# power.net
KiCad netlist of a schematic drawn in EAGLE
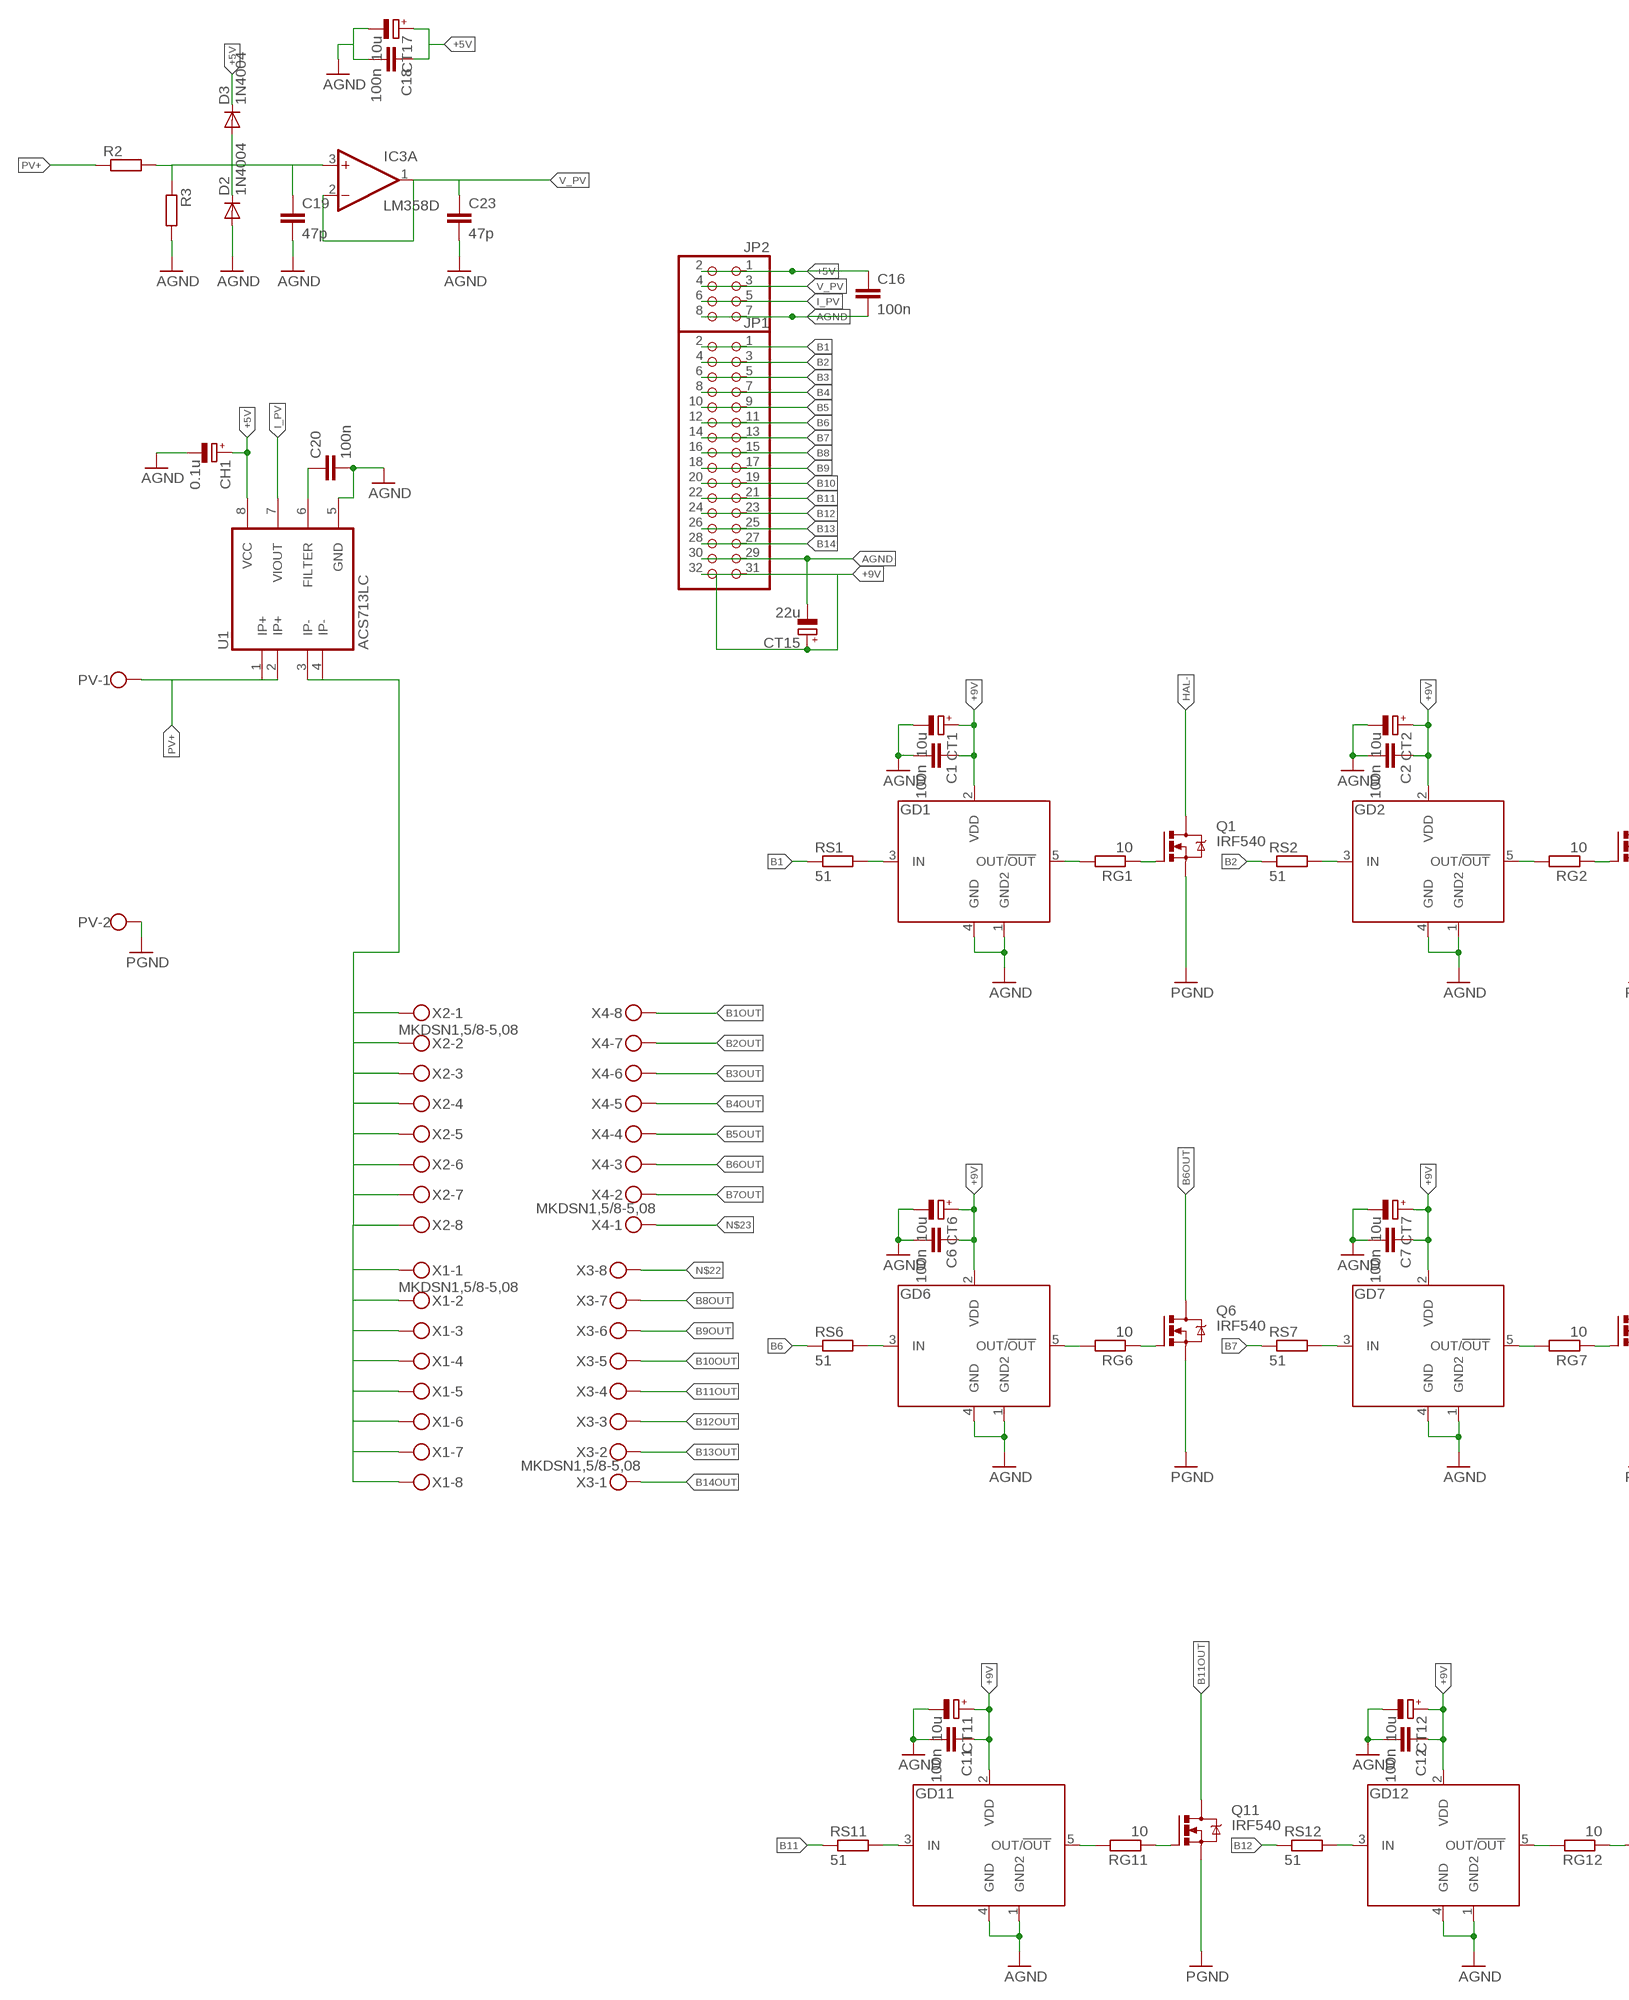
[diagram p0: schematic, sheet 1, part 1 of 2]
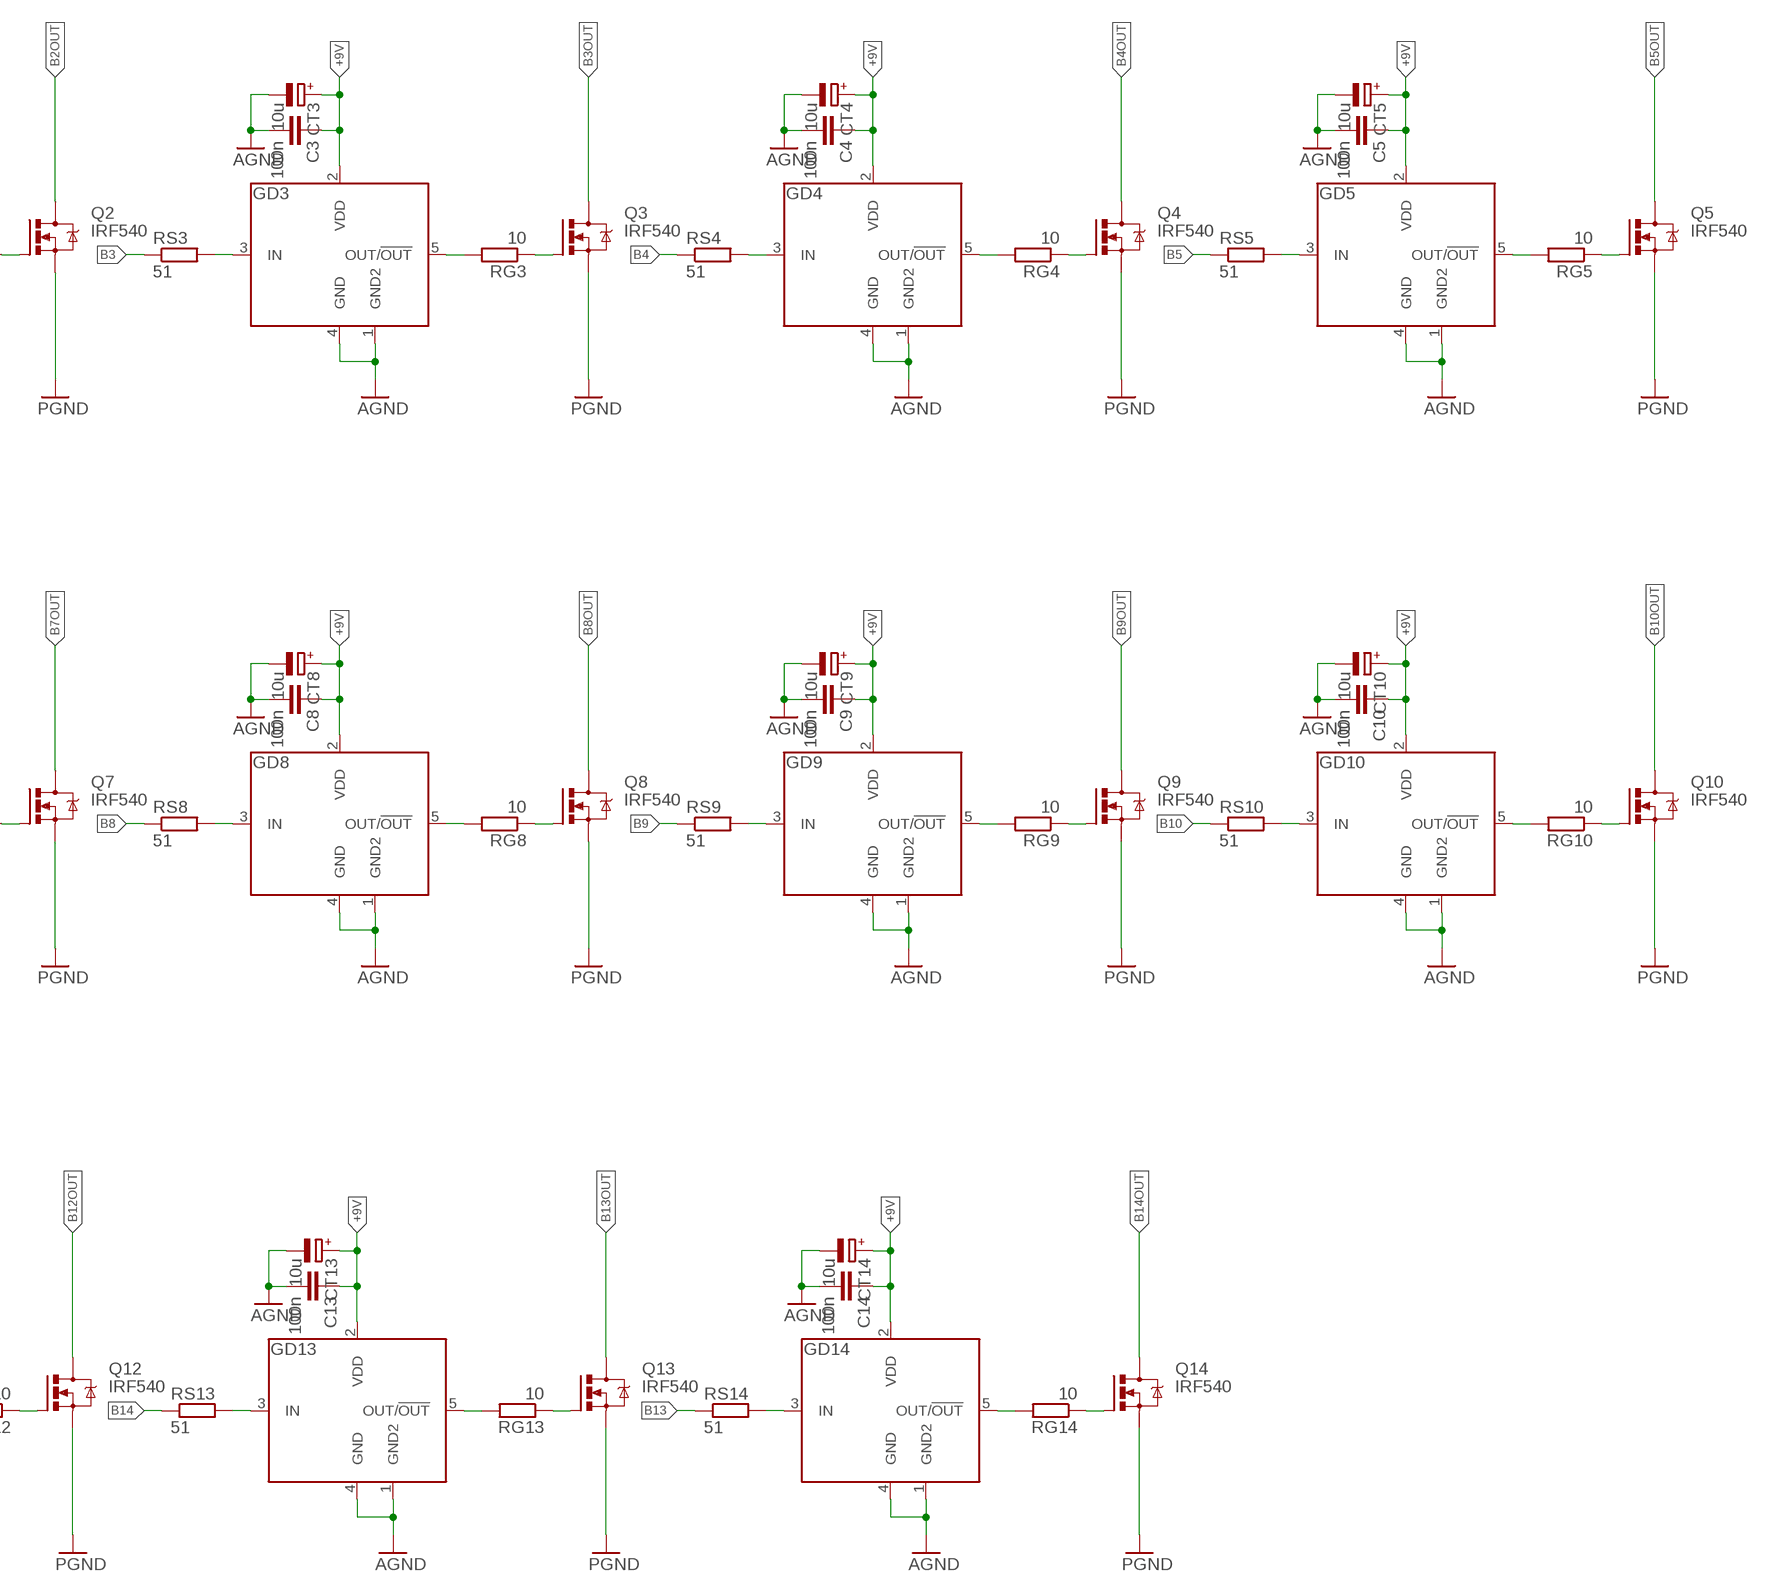
[diagram p1: schematic, sheet 1, part 2 of 2]

(export (version "E")
  (design (tool "Eeschema 10.0.6"))
  (components
    (comp (ref "C1")
      (value "100n")
      (footprint "eagle-import:C0603")
      (libsource (lib "eagle-import") (part "C-EUC0603"))
    )
    (comp (ref "C2")
      (value "100n")
      (footprint "eagle-import:C0603")
      (libsource (lib "eagle-import") (part "C-EUC0603"))
    )
    (comp (ref "C3")
      (value "100n")
      (footprint "eagle-import:C0603")
      (libsource (lib "eagle-import") (part "C-EUC0603"))
    )
    (comp (ref "C4")
      (value "100n")
      (footprint "eagle-import:C0603")
      (libsource (lib "eagle-import") (part "C-EUC0603"))
    )
    (comp (ref "C5")
      (value "100n")
      (footprint "eagle-import:C0603")
      (libsource (lib "eagle-import") (part "C-EUC0603"))
    )
    (comp (ref "C6")
      (value "100n")
      (footprint "eagle-import:C0603")
      (libsource (lib "eagle-import") (part "C-EUC0603"))
    )
    (comp (ref "C7")
      (value "100n")
      (footprint "eagle-import:C0603")
      (libsource (lib "eagle-import") (part "C-EUC0603"))
    )
    (comp (ref "C8")
      (value "100n")
      (footprint "eagle-import:C0603")
      (libsource (lib "eagle-import") (part "C-EUC0603"))
    )
    (comp (ref "C9")
      (value "100n")
      (footprint "eagle-import:C0603")
      (libsource (lib "eagle-import") (part "C-EUC0603"))
    )
    (comp (ref "C10")
      (value "100n")
      (footprint "eagle-import:C0603")
      (libsource (lib "eagle-import") (part "C-EUC0603"))
    )
    (comp (ref "C11")
      (value "100n")
      (footprint "eagle-import:C0603")
      (libsource (lib "eagle-import") (part "C-EUC0603"))
    )
    (comp (ref "C12")
      (value "100n")
      (footprint "eagle-import:C0603")
      (libsource (lib "eagle-import") (part "C-EUC0603"))
    )
    (comp (ref "C13")
      (value "100n")
      (footprint "eagle-import:C0603")
      (libsource (lib "eagle-import") (part "C-EUC0603"))
    )
    (comp (ref "C14")
      (value "100n")
      (footprint "eagle-import:C0603")
      (libsource (lib "eagle-import") (part "C-EUC0603"))
    )
    (comp (ref "C16")
      (value "100n")
      (footprint "eagle-import:C0603")
      (libsource (lib "eagle-import") (part "C-EUC0603"))
    )
    (comp (ref "C18")
      (value "100n")
      (footprint "eagle-import:C0603")
      (libsource (lib "eagle-import") (part "C-EUC0603"))
    )
    (comp (ref "C19")
      (value "47p")
      (footprint "eagle-import:C0603")
      (libsource (lib "eagle-import") (part "C-EUC0603"))
    )
    (comp (ref "C20")
      (value "100n")
      (footprint "eagle-import:C0603")
      (libsource (lib "eagle-import") (part "C-EUC0603"))
    )
    (comp (ref "C23")
      (value "47p")
      (footprint "eagle-import:C0603")
      (libsource (lib "eagle-import") (part "C-EUC0603"))
    )
    (comp (ref "CH1")
      (value "0.1u")
      (footprint "eagle-import:B_3528-21W")
      (libsource (lib "eagle-import") (part "CPOL-EUB/3528-21W"))
    )
    (comp (ref "CT1")
      (value "10u")
      (footprint "eagle-import:B_3528-21W")
      (libsource (lib "eagle-import") (part "CPOL-EUB/3528-21W"))
    )
    (comp (ref "CT2")
      (value "10u")
      (footprint "eagle-import:B_3528-21W")
      (libsource (lib "eagle-import") (part "CPOL-EUB/3528-21W"))
    )
    (comp (ref "CT3")
      (value "10u")
      (footprint "eagle-import:B_3528-21W")
      (libsource (lib "eagle-import") (part "CPOL-EUB/3528-21W"))
    )
    (comp (ref "CT4")
      (value "10u")
      (footprint "eagle-import:B_3528-21W")
      (libsource (lib "eagle-import") (part "CPOL-EUB/3528-21W"))
    )
    (comp (ref "CT5")
      (value "10u")
      (footprint "eagle-import:B_3528-21W")
      (libsource (lib "eagle-import") (part "CPOL-EUB/3528-21W"))
    )
    (comp (ref "CT6")
      (value "10u")
      (footprint "eagle-import:B_3528-21W")
      (libsource (lib "eagle-import") (part "CPOL-EUB/3528-21W"))
    )
    (comp (ref "CT7")
      (value "10u")
      (footprint "eagle-import:B_3528-21W")
      (libsource (lib "eagle-import") (part "CPOL-EUB/3528-21W"))
    )
    (comp (ref "CT8")
      (value "10u")
      (footprint "eagle-import:B_3528-21W")
      (libsource (lib "eagle-import") (part "CPOL-EUB/3528-21W"))
    )
    (comp (ref "CT9")
      (value "10u")
      (footprint "eagle-import:B_3528-21W")
      (libsource (lib "eagle-import") (part "CPOL-EUB/3528-21W"))
    )
    (comp (ref "CT10")
      (value "10u")
      (footprint "eagle-import:B_3528-21W")
      (libsource (lib "eagle-import") (part "CPOL-EUB/3528-21W"))
    )
    (comp (ref "CT11")
      (value "10u")
      (footprint "eagle-import:B_3528-21W")
      (libsource (lib "eagle-import") (part "CPOL-EUB/3528-21W"))
    )
    (comp (ref "CT12")
      (value "10u")
      (footprint "eagle-import:B_3528-21W")
      (libsource (lib "eagle-import") (part "CPOL-EUB/3528-21W"))
    )
    (comp (ref "CT13")
      (value "10u")
      (footprint "eagle-import:B_3528-21W")
      (libsource (lib "eagle-import") (part "CPOL-EUB/3528-21W"))
    )
    (comp (ref "CT14")
      (value "10u")
      (footprint "eagle-import:B_3528-21W")
      (libsource (lib "eagle-import") (part "CPOL-EUB/3528-21W"))
    )
    (comp (ref "CT15")
      (value "22u")
      (footprint "eagle-import:B_3528-21W")
      (libsource (lib "eagle-import") (part "CPOL-EUB/3528-21W"))
    )
    (comp (ref "CT17")
      (value "10u")
      (footprint "eagle-import:B_3528-21W")
      (libsource (lib "eagle-import") (part "CPOL-EUB/3528-21W"))
    )
    (comp (ref "D2")
      (value "1N4004")
      (footprint "eagle-import:DO214AC")
      (libsource (lib "eagle-import") (part "1N4004"))
    )
    (comp (ref "D3")
      (value "1N4004")
      (footprint "eagle-import:DO214AC")
      (libsource (lib "eagle-import") (part "1N4004"))
    )
    (comp (ref "GD1")
      (value "MCP1415/16")
      (footprint "eagle-import:SOT23-5L")
      (libsource (lib "eagle-import") (part "MCP1415/16"))
    )
    (comp (ref "GD2")
      (value "MCP1415/16")
      (footprint "eagle-import:SOT23-5L")
      (libsource (lib "eagle-import") (part "MCP1415/16"))
    )
    (comp (ref "GD3")
      (value "MCP1415/16")
      (footprint "eagle-import:SOT23-5L")
      (libsource (lib "eagle-import") (part "MCP1415/16"))
    )
    (comp (ref "GD4")
      (value "MCP1415/16")
      (footprint "eagle-import:SOT23-5L")
      (libsource (lib "eagle-import") (part "MCP1415/16"))
    )
    (comp (ref "GD5")
      (value "MCP1415/16")
      (footprint "eagle-import:SOT23-5L")
      (libsource (lib "eagle-import") (part "MCP1415/16"))
    )
    (comp (ref "GD6")
      (value "MCP1415/16")
      (footprint "eagle-import:SOT23-5L")
      (libsource (lib "eagle-import") (part "MCP1415/16"))
    )
    (comp (ref "GD7")
      (value "MCP1415/16")
      (footprint "eagle-import:SOT23-5L")
      (libsource (lib "eagle-import") (part "MCP1415/16"))
    )
    (comp (ref "GD8")
      (value "MCP1415/16")
      (footprint "eagle-import:SOT23-5L")
      (libsource (lib "eagle-import") (part "MCP1415/16"))
    )
    (comp (ref "GD9")
      (value "MCP1415/16")
      (footprint "eagle-import:SOT23-5L")
      (libsource (lib "eagle-import") (part "MCP1415/16"))
    )
    (comp (ref "GD10")
      (value "MCP1415/16")
      (footprint "eagle-import:SOT23-5L")
      (libsource (lib "eagle-import") (part "MCP1415/16"))
    )
    (comp (ref "GD11")
      (value "MCP1415/16")
      (footprint "eagle-import:SOT23-5L")
      (libsource (lib "eagle-import") (part "MCP1415/16"))
    )
    (comp (ref "GD12")
      (value "MCP1415/16")
      (footprint "eagle-import:SOT23-5L")
      (libsource (lib "eagle-import") (part "MCP1415/16"))
    )
    (comp (ref "GD13")
      (value "MCP1415/16")
      (footprint "eagle-import:SOT23-5L")
      (libsource (lib "eagle-import") (part "MCP1415/16"))
    )
    (comp (ref "GD14")
      (value "MCP1415/16")
      (footprint "eagle-import:SOT23-5L")
      (libsource (lib "eagle-import") (part "MCP1415/16"))
    )
    (comp (ref "IC3")
      (value "LM358D")
      (footprint "eagle-import:SO08")
      (libsource (lib "eagle-import") (part "LM358D"))
    )
    (comp (ref "JP1")
      (value "PINHD-2X16")
      (footprint "eagle-import:2X16")
      (libsource (lib "eagle-import") (part "PINHD-2X16"))
    )
    (comp (ref "JP2")
      (value "PINHD-2X4")
      (footprint "eagle-import:2X04")
      (libsource (lib "eagle-import") (part "PINHD-2X4"))
    )
    (comp (ref "PV")
      (value "W237-102")
      (footprint "eagle-import:W237-102")
      (fields (field (name "MPN") "237-102"))
      (libsource (lib "eagle-import") (part "W237-102"))
    )
    (comp (ref "Q1")
      (value "IRF540")
      (footprint "eagle-import:TO220BV")
      (libsource (lib "eagle-import") (part "IRF540"))
    )
    (comp (ref "Q2")
      (value "IRF540")
      (footprint "eagle-import:TO220BV")
      (libsource (lib "eagle-import") (part "IRF540"))
    )
    (comp (ref "Q3")
      (value "IRF540")
      (footprint "eagle-import:TO220BV")
      (libsource (lib "eagle-import") (part "IRF540"))
    )
    (comp (ref "Q4")
      (value "IRF540")
      (footprint "eagle-import:TO220BV")
      (libsource (lib "eagle-import") (part "IRF540"))
    )
    (comp (ref "Q5")
      (value "IRF540")
      (footprint "eagle-import:TO220BV")
      (libsource (lib "eagle-import") (part "IRF540"))
    )
    (comp (ref "Q6")
      (value "IRF540")
      (footprint "eagle-import:TO220BV")
      (libsource (lib "eagle-import") (part "IRF540"))
    )
    (comp (ref "Q7")
      (value "IRF540")
      (footprint "eagle-import:TO220BV")
      (libsource (lib "eagle-import") (part "IRF540"))
    )
    (comp (ref "Q8")
      (value "IRF540")
      (footprint "eagle-import:TO220BV")
      (libsource (lib "eagle-import") (part "IRF540"))
    )
    (comp (ref "Q9")
      (value "IRF540")
      (footprint "eagle-import:TO220BV")
      (libsource (lib "eagle-import") (part "IRF540"))
    )
    (comp (ref "Q10")
      (value "IRF540")
      (footprint "eagle-import:TO220BV")
      (libsource (lib "eagle-import") (part "IRF540"))
    )
    (comp (ref "Q11")
      (value "IRF540")
      (footprint "eagle-import:TO220BV")
      (libsource (lib "eagle-import") (part "IRF540"))
    )
    (comp (ref "Q12")
      (value "IRF540")
      (footprint "eagle-import:TO220BV")
      (libsource (lib "eagle-import") (part "IRF540"))
    )
    (comp (ref "Q13")
      (value "IRF540")
      (footprint "eagle-import:TO220BV")
      (libsource (lib "eagle-import") (part "IRF540"))
    )
    (comp (ref "Q14")
      (value "IRF540")
      (footprint "eagle-import:TO220BV")
      (libsource (lib "eagle-import") (part "IRF540"))
    )
    (comp (ref "R2")
      (value "R-EU_R1206")
      (footprint "eagle-import:R1206")
      (libsource (lib "eagle-import") (part "R-EU_R1206"))
    )
    (comp (ref "R3")
      (value "R-EU_R1206")
      (footprint "eagle-import:R1206")
      (libsource (lib "eagle-import") (part "R-EU_R1206"))
    )
    (comp (ref "RG1")
      (value "10")
      (footprint "eagle-import:R1206")
      (libsource (lib "eagle-import") (part "R-EU_R1206"))
    )
    (comp (ref "RG2")
      (value "10")
      (footprint "eagle-import:R1206")
      (libsource (lib "eagle-import") (part "R-EU_R1206"))
    )
    (comp (ref "RG3")
      (value "10")
      (footprint "eagle-import:R1206")
      (libsource (lib "eagle-import") (part "R-EU_R1206"))
    )
    (comp (ref "RG4")
      (value "10")
      (footprint "eagle-import:R1206")
      (libsource (lib "eagle-import") (part "R-EU_R1206"))
    )
    (comp (ref "RG5")
      (value "10")
      (footprint "eagle-import:R1206")
      (libsource (lib "eagle-import") (part "R-EU_R1206"))
    )
    (comp (ref "RG6")
      (value "10")
      (footprint "eagle-import:R1206")
      (libsource (lib "eagle-import") (part "R-EU_R1206"))
    )
    (comp (ref "RG7")
      (value "10")
      (footprint "eagle-import:R1206")
      (libsource (lib "eagle-import") (part "R-EU_R1206"))
    )
    (comp (ref "RG8")
      (value "10")
      (footprint "eagle-import:R1206")
      (libsource (lib "eagle-import") (part "R-EU_R1206"))
    )
    (comp (ref "RG9")
      (value "10")
      (footprint "eagle-import:R1206")
      (libsource (lib "eagle-import") (part "R-EU_R1206"))
    )
    (comp (ref "RG10")
      (value "10")
      (footprint "eagle-import:R1206")
      (libsource (lib "eagle-import") (part "R-EU_R1206"))
    )
    (comp (ref "RG11")
      (value "10")
      (footprint "eagle-import:R1206")
      (libsource (lib "eagle-import") (part "R-EU_R1206"))
    )
    (comp (ref "RG12")
      (value "10")
      (footprint "eagle-import:R1206")
      (libsource (lib "eagle-import") (part "R-EU_R1206"))
    )
    (comp (ref "RG13")
      (value "10")
      (footprint "eagle-import:R1206")
      (libsource (lib "eagle-import") (part "R-EU_R1206"))
    )
    (comp (ref "RG14")
      (value "10")
      (footprint "eagle-import:R1206")
      (libsource (lib "eagle-import") (part "R-EU_R1206"))
    )
    (comp (ref "RS1")
      (value "51")
      (footprint "eagle-import:R1206")
      (libsource (lib "eagle-import") (part "R-EU_R1206"))
    )
    (comp (ref "RS2")
      (value "51")
      (footprint "eagle-import:R1206")
      (libsource (lib "eagle-import") (part "R-EU_R1206"))
    )
    (comp (ref "RS3")
      (value "51")
      (footprint "eagle-import:R1206")
      (libsource (lib "eagle-import") (part "R-EU_R1206"))
    )
    (comp (ref "RS4")
      (value "51")
      (footprint "eagle-import:R1206")
      (libsource (lib "eagle-import") (part "R-EU_R1206"))
    )
    (comp (ref "RS5")
      (value "51")
      (footprint "eagle-import:R1206")
      (libsource (lib "eagle-import") (part "R-EU_R1206"))
    )
    (comp (ref "RS6")
      (value "51")
      (footprint "eagle-import:R1206")
      (libsource (lib "eagle-import") (part "R-EU_R1206"))
    )
    (comp (ref "RS7")
      (value "51")
      (footprint "eagle-import:R1206")
      (libsource (lib "eagle-import") (part "R-EU_R1206"))
    )
    (comp (ref "RS8")
      (value "51")
      (footprint "eagle-import:R1206")
      (libsource (lib "eagle-import") (part "R-EU_R1206"))
    )
    (comp (ref "RS9")
      (value "51")
      (footprint "eagle-import:R1206")
      (libsource (lib "eagle-import") (part "R-EU_R1206"))
    )
    (comp (ref "RS10")
      (value "51")
      (footprint "eagle-import:R1206")
      (libsource (lib "eagle-import") (part "R-EU_R1206"))
    )
    (comp (ref "RS11")
      (value "51")
      (footprint "eagle-import:R1206")
      (libsource (lib "eagle-import") (part "R-EU_R1206"))
    )
    (comp (ref "RS12")
      (value "51")
      (footprint "eagle-import:R1206")
      (libsource (lib "eagle-import") (part "R-EU_R1206"))
    )
    (comp (ref "RS13")
      (value "51")
      (footprint "eagle-import:R1206")
      (libsource (lib "eagle-import") (part "R-EU_R1206"))
    )
    (comp (ref "RS14")
      (value "51")
      (footprint "eagle-import:R1206")
      (libsource (lib "eagle-import") (part "R-EU_R1206"))
    )
    (comp (ref "U1")
      (value "ACS713LC")
      (footprint "eagle-import:SO08")
      (libsource (lib "eagle-import") (part "ACS713LC"))
    )
    (comp (ref "X1")
      (value "MKDSN1,5/8-5,08")
      (footprint "eagle-import:MKDSN1,5_8-5,08")
      (libsource (lib "eagle-import") (part "MKDSN1,5/8-5,08"))
    )
    (comp (ref "X2")
      (value "MKDSN1,5/8-5,08")
      (footprint "eagle-import:MKDSN1,5_8-5,08")
      (libsource (lib "eagle-import") (part "MKDSN1,5/8-5,08"))
    )
    (comp (ref "X3")
      (value "MKDSN1,5/8-5,08")
      (footprint "eagle-import:MKDSN1,5_8-5,08")
      (libsource (lib "eagle-import") (part "MKDSN1,5/8-5,08"))
    )
    (comp (ref "X4")
      (value "MKDSN1,5/8-5,08")
      (footprint "eagle-import:MKDSN1,5_8-5,08")
      (libsource (lib "eagle-import") (part "MKDSN1,5/8-5,08"))
    )
  )
  (nets
    (net (code "1") (name "+5V") (class "Default")
      (node (ref "C16") (pin "1") (pinfunction "1_1") (pintype "passive"))
      (node (ref "C18") (pin "1") (pinfunction "1_1") (pintype "passive"))
      (node (ref "CH1") (pin "+") (pinfunction "+_+") (pintype "passive"))
      (node (ref "CT17") (pin "+") (pinfunction "+_+") (pintype "passive"))
      (node (ref "D3") (pin "C") (pinfunction "C_C") (pintype "passive"))
      (node (ref "JP2") (pin "1") (pinfunction "1_1") (pintype "passive"))
      (node (ref "JP2") (pin "2") (pinfunction "2_2") (pintype "passive"))
      (node (ref "U1") (pin "8") (pinfunction "VCC_8") (pintype "power_in"))
    )
    (net (code "2") (name "+9V") (class "Default")
      (node (ref "C1") (pin "1") (pinfunction "1_1") (pintype "passive"))
      (node (ref "C10") (pin "1") (pinfunction "1_1") (pintype "passive"))
      (node (ref "C11") (pin "1") (pinfunction "1_1") (pintype "passive"))
      (node (ref "C12") (pin "1") (pinfunction "1_1") (pintype "passive"))
      (node (ref "C13") (pin "1") (pinfunction "1_1") (pintype "passive"))
      (node (ref "C14") (pin "1") (pinfunction "1_1") (pintype "passive"))
      (node (ref "C2") (pin "1") (pinfunction "1_1") (pintype "passive"))
      (node (ref "C3") (pin "1") (pinfunction "1_1") (pintype "passive"))
      (node (ref "C4") (pin "1") (pinfunction "1_1") (pintype "passive"))
      (node (ref "C5") (pin "1") (pinfunction "1_1") (pintype "passive"))
      (node (ref "C6") (pin "1") (pinfunction "1_1") (pintype "passive"))
      (node (ref "C7") (pin "1") (pinfunction "1_1") (pintype "passive"))
      (node (ref "C8") (pin "1") (pinfunction "1_1") (pintype "passive"))
      (node (ref "C9") (pin "1") (pinfunction "1_1") (pintype "passive"))
      (node (ref "CT1") (pin "+") (pinfunction "+_+") (pintype "passive"))
      (node (ref "CT10") (pin "+") (pinfunction "+_+") (pintype "passive"))
      (node (ref "CT11") (pin "+") (pinfunction "+_+") (pintype "passive"))
      (node (ref "CT12") (pin "+") (pinfunction "+_+") (pintype "passive"))
      (node (ref "CT13") (pin "+") (pinfunction "+_+") (pintype "passive"))
      (node (ref "CT14") (pin "+") (pinfunction "+_+") (pintype "passive"))
      (node (ref "CT15") (pin "+") (pinfunction "+_+") (pintype "passive"))
      (node (ref "CT2") (pin "+") (pinfunction "+_+") (pintype "passive"))
      (node (ref "CT3") (pin "+") (pinfunction "+_+") (pintype "passive"))
      (node (ref "CT4") (pin "+") (pinfunction "+_+") (pintype "passive"))
      (node (ref "CT5") (pin "+") (pinfunction "+_+") (pintype "passive"))
      (node (ref "CT6") (pin "+") (pinfunction "+_+") (pintype "passive"))
      (node (ref "CT7") (pin "+") (pinfunction "+_+") (pintype "passive"))
      (node (ref "CT8") (pin "+") (pinfunction "+_+") (pintype "passive"))
      (node (ref "CT9") (pin "+") (pinfunction "+_+") (pintype "passive"))
      (node (ref "GD1") (pin "2") (pinfunction "VDD_2") (pintype "power_in"))
      (node (ref "GD10") (pin "2") (pinfunction "VDD_2") (pintype "power_in"))
      (node (ref "GD11") (pin "2") (pinfunction "VDD_2") (pintype "power_in"))
      (node (ref "GD12") (pin "2") (pinfunction "VDD_2") (pintype "power_in"))
      (node (ref "GD13") (pin "2") (pinfunction "VDD_2") (pintype "power_in"))
      (node (ref "GD14") (pin "2") (pinfunction "VDD_2") (pintype "power_in"))
      (node (ref "GD2") (pin "2") (pinfunction "VDD_2") (pintype "power_in"))
      (node (ref "GD3") (pin "2") (pinfunction "VDD_2") (pintype "power_in"))
      (node (ref "GD4") (pin "2") (pinfunction "VDD_2") (pintype "power_in"))
      (node (ref "GD5") (pin "2") (pinfunction "VDD_2") (pintype "power_in"))
      (node (ref "GD6") (pin "2") (pinfunction "VDD_2") (pintype "power_in"))
      (node (ref "GD7") (pin "2") (pinfunction "VDD_2") (pintype "power_in"))
      (node (ref "GD8") (pin "2") (pinfunction "VDD_2") (pintype "power_in"))
      (node (ref "GD9") (pin "2") (pinfunction "VDD_2") (pintype "power_in"))
      (node (ref "JP1") (pin "31") (pinfunction "31_31") (pintype "passive"))
      (node (ref "JP1") (pin "32") (pinfunction "32_32") (pintype "passive"))
    )
    (net (code "3") (name "AGND") (class "Default")
      (node (ref "C1") (pin "2") (pinfunction "2_2") (pintype "passive"))
      (node (ref "C10") (pin "2") (pinfunction "2_2") (pintype "passive"))
      (node (ref "C11") (pin "2") (pinfunction "2_2") (pintype "passive"))
      (node (ref "C12") (pin "2") (pinfunction "2_2") (pintype "passive"))
      (node (ref "C13") (pin "2") (pinfunction "2_2") (pintype "passive"))
      (node (ref "C14") (pin "2") (pinfunction "2_2") (pintype "passive"))
      (node (ref "C16") (pin "2") (pinfunction "2_2") (pintype "passive"))
      (node (ref "C18") (pin "2") (pinfunction "2_2") (pintype "passive"))
      (node (ref "C19") (pin "2") (pinfunction "2_2") (pintype "passive"))
      (node (ref "C2") (pin "2") (pinfunction "2_2") (pintype "passive"))
      (node (ref "C20") (pin "2") (pinfunction "2_2") (pintype "passive"))
      (node (ref "C23") (pin "2") (pinfunction "2_2") (pintype "passive"))
      (node (ref "C3") (pin "2") (pinfunction "2_2") (pintype "passive"))
      (node (ref "C4") (pin "2") (pinfunction "2_2") (pintype "passive"))
      (node (ref "C5") (pin "2") (pinfunction "2_2") (pintype "passive"))
      (node (ref "C6") (pin "2") (pinfunction "2_2") (pintype "passive"))
      (node (ref "C7") (pin "2") (pinfunction "2_2") (pintype "passive"))
      (node (ref "C8") (pin "2") (pinfunction "2_2") (pintype "passive"))
      (node (ref "C9") (pin "2") (pinfunction "2_2") (pintype "passive"))
      (node (ref "CH1") (pin "-") (pinfunction "-_-") (pintype "passive"))
      (node (ref "CT1") (pin "-") (pinfunction "-_-") (pintype "passive"))
      (node (ref "CT10") (pin "-") (pinfunction "-_-") (pintype "passive"))
      (node (ref "CT11") (pin "-") (pinfunction "-_-") (pintype "passive"))
      (node (ref "CT12") (pin "-") (pinfunction "-_-") (pintype "passive"))
      (node (ref "CT13") (pin "-") (pinfunction "-_-") (pintype "passive"))
      (node (ref "CT14") (pin "-") (pinfunction "-_-") (pintype "passive"))
      (node (ref "CT15") (pin "-") (pinfunction "-_-") (pintype "passive"))
      (node (ref "CT17") (pin "-") (pinfunction "-_-") (pintype "passive"))
      (node (ref "CT2") (pin "-") (pinfunction "-_-") (pintype "passive"))
      (node (ref "CT3") (pin "-") (pinfunction "-_-") (pintype "passive"))
      (node (ref "CT4") (pin "-") (pinfunction "-_-") (pintype "passive"))
      (node (ref "CT5") (pin "-") (pinfunction "-_-") (pintype "passive"))
      (node (ref "CT6") (pin "-") (pinfunction "-_-") (pintype "passive"))
      (node (ref "CT7") (pin "-") (pinfunction "-_-") (pintype "passive"))
      (node (ref "CT8") (pin "-") (pinfunction "-_-") (pintype "passive"))
      (node (ref "CT9") (pin "-") (pinfunction "-_-") (pintype "passive"))
      (node (ref "D2") (pin "A") (pinfunction "A_A") (pintype "passive"))
      (node (ref "GD1") (pin "1") (pinfunction "GND2_1") (pintype "bidirectional"))
      (node (ref "GD1") (pin "4") (pinfunction "GND_4") (pintype "power_in"))
      (node (ref "GD10") (pin "1") (pinfunction "GND2_1") (pintype "bidirectional"))
      (node (ref "GD10") (pin "4") (pinfunction "GND_4") (pintype "power_in"))
      (node (ref "GD11") (pin "1") (pinfunction "GND2_1") (pintype "bidirectional"))
      (node (ref "GD11") (pin "4") (pinfunction "GND_4") (pintype "power_in"))
      (node (ref "GD12") (pin "1") (pinfunction "GND2_1") (pintype "bidirectional"))
      (node (ref "GD12") (pin "4") (pinfunction "GND_4") (pintype "power_in"))
      (node (ref "GD13") (pin "1") (pinfunction "GND2_1") (pintype "bidirectional"))
      (node (ref "GD13") (pin "4") (pinfunction "GND_4") (pintype "power_in"))
      (node (ref "GD14") (pin "1") (pinfunction "GND2_1") (pintype "bidirectional"))
      (node (ref "GD14") (pin "4") (pinfunction "GND_4") (pintype "power_in"))
      (node (ref "GD2") (pin "1") (pinfunction "GND2_1") (pintype "bidirectional"))
      (node (ref "GD2") (pin "4") (pinfunction "GND_4") (pintype "power_in"))
      (node (ref "GD3") (pin "1") (pinfunction "GND2_1") (pintype "bidirectional"))
      (node (ref "GD3") (pin "4") (pinfunction "GND_4") (pintype "power_in"))
      (node (ref "GD4") (pin "1") (pinfunction "GND2_1") (pintype "bidirectional"))
      (node (ref "GD4") (pin "4") (pinfunction "GND_4") (pintype "power_in"))
      (node (ref "GD5") (pin "1") (pinfunction "GND2_1") (pintype "bidirectional"))
      (node (ref "GD5") (pin "4") (pinfunction "GND_4") (pintype "power_in"))
      (node (ref "GD6") (pin "1") (pinfunction "GND2_1") (pintype "bidirectional"))
      (node (ref "GD6") (pin "4") (pinfunction "GND_4") (pintype "power_in"))
      (node (ref "GD7") (pin "1") (pinfunction "GND2_1") (pintype "bidirectional"))
      (node (ref "GD7") (pin "4") (pinfunction "GND_4") (pintype "power_in"))
      (node (ref "GD8") (pin "1") (pinfunction "GND2_1") (pintype "bidirectional"))
      (node (ref "GD8") (pin "4") (pinfunction "GND_4") (pintype "power_in"))
      (node (ref "GD9") (pin "1") (pinfunction "GND2_1") (pintype "bidirectional"))
      (node (ref "GD9") (pin "4") (pinfunction "GND_4") (pintype "power_in"))
      (node (ref "JP1") (pin "29") (pinfunction "29_29") (pintype "passive"))
      (node (ref "JP1") (pin "30") (pinfunction "30_30") (pintype "passive"))
      (node (ref "JP2") (pin "7") (pinfunction "7_7") (pintype "passive"))
      (node (ref "JP2") (pin "8") (pinfunction "8_8") (pintype "passive"))
      (node (ref "R3") (pin "2") (pinfunction "2_2") (pintype "passive"))
      (node (ref "U1") (pin "5") (pinfunction "GND_5") (pintype "power_in"))
    )
    (net (code "4") (name "B1") (class "Default")
      (node (ref "JP1") (pin "1") (pinfunction "1_1") (pintype "passive"))
      (node (ref "JP1") (pin "2") (pinfunction "2_2") (pintype "passive"))
      (node (ref "RS1") (pin "1") (pinfunction "1_1") (pintype "passive"))
    )
    (net (code "5") (name "B1OUT") (class "Default")
      (node (ref "X4") (pin "8") (pinfunction "KL_8") (pintype "passive"))
    )
    (net (code "6") (name "B2") (class "Default")
      (node (ref "JP1") (pin "3") (pinfunction "3_3") (pintype "passive"))
      (node (ref "JP1") (pin "4") (pinfunction "4_4") (pintype "passive"))
      (node (ref "RS2") (pin "1") (pinfunction "1_1") (pintype "passive"))
    )
    (net (code "7") (name "B2OUT") (class "Default")
      (node (ref "Q2") (pin "D") (pinfunction "D_D") (pintype "passive"))
      (node (ref "X4") (pin "7") (pinfunction "KL_7") (pintype "passive"))
    )
    (net (code "8") (name "B3") (class "Default")
      (node (ref "JP1") (pin "5") (pinfunction "5_5") (pintype "passive"))
      (node (ref "JP1") (pin "6") (pinfunction "6_6") (pintype "passive"))
      (node (ref "RS3") (pin "1") (pinfunction "1_1") (pintype "passive"))
    )
    (net (code "9") (name "B3OUT") (class "Default")
      (node (ref "Q3") (pin "D") (pinfunction "D_D") (pintype "passive"))
      (node (ref "X4") (pin "6") (pinfunction "KL_6") (pintype "passive"))
    )
    (net (code "10") (name "B4") (class "Default")
      (node (ref "JP1") (pin "7") (pinfunction "7_7") (pintype "passive"))
      (node (ref "JP1") (pin "8") (pinfunction "8_8") (pintype "passive"))
      (node (ref "RS4") (pin "1") (pinfunction "1_1") (pintype "passive"))
    )
    (net (code "11") (name "B4OUT") (class "Default")
      (node (ref "Q4") (pin "D") (pinfunction "D_D") (pintype "passive"))
      (node (ref "X4") (pin "5") (pinfunction "KL_5") (pintype "passive"))
    )
    (net (code "12") (name "B5") (class "Default")
      (node (ref "JP1") (pin "10") (pinfunction "10_10") (pintype "passive"))
      (node (ref "JP1") (pin "9") (pinfunction "9_9") (pintype "passive"))
      (node (ref "RS5") (pin "1") (pinfunction "1_1") (pintype "passive"))
    )
    (net (code "13") (name "B5OUT") (class "Default")
      (node (ref "Q5") (pin "D") (pinfunction "D_D") (pintype "passive"))
      (node (ref "X4") (pin "4") (pinfunction "KL_4") (pintype "passive"))
    )
    (net (code "14") (name "B6") (class "Default")
      (node (ref "JP1") (pin "11") (pinfunction "11_11") (pintype "passive"))
      (node (ref "JP1") (pin "12") (pinfunction "12_12") (pintype "passive"))
      (node (ref "RS6") (pin "1") (pinfunction "1_1") (pintype "passive"))
    )
    (net (code "15") (name "B6OUT") (class "Default")
      (node (ref "Q6") (pin "D") (pinfunction "D_D") (pintype "passive"))
      (node (ref "X4") (pin "3") (pinfunction "KL_3") (pintype "passive"))
    )
    (net (code "16") (name "B7") (class "Default")
      (node (ref "JP1") (pin "13") (pinfunction "13_13") (pintype "passive"))
      (node (ref "JP1") (pin "14") (pinfunction "14_14") (pintype "passive"))
      (node (ref "RS7") (pin "1") (pinfunction "1_1") (pintype "passive"))
    )
    (net (code "17") (name "B7OUT") (class "Default")
      (node (ref "Q7") (pin "D") (pinfunction "D_D") (pintype "passive"))
      (node (ref "X4") (pin "2") (pinfunction "KL_2") (pintype "passive"))
    )
    (net (code "18") (name "B8") (class "Default")
      (node (ref "JP1") (pin "15") (pinfunction "15_15") (pintype "passive"))
      (node (ref "JP1") (pin "16") (pinfunction "16_16") (pintype "passive"))
      (node (ref "RS8") (pin "1") (pinfunction "1_1") (pintype "passive"))
    )
    (net (code "19") (name "B8OUT") (class "Default")
      (node (ref "Q8") (pin "D") (pinfunction "D_D") (pintype "passive"))
      (node (ref "X3") (pin "7") (pinfunction "KL_7") (pintype "passive"))
    )
    (net (code "20") (name "B9") (class "Default")
      (node (ref "JP1") (pin "17") (pinfunction "17_17") (pintype "passive"))
      (node (ref "JP1") (pin "18") (pinfunction "18_18") (pintype "passive"))
      (node (ref "RS9") (pin "1") (pinfunction "1_1") (pintype "passive"))
    )
    (net (code "21") (name "B9OUT") (class "Default")
      (node (ref "Q9") (pin "D") (pinfunction "D_D") (pintype "passive"))
      (node (ref "X3") (pin "6") (pinfunction "KL_6") (pintype "passive"))
    )
    (net (code "22") (name "B10") (class "Default")
      (node (ref "JP1") (pin "19") (pinfunction "19_19") (pintype "passive"))
      (node (ref "JP1") (pin "20") (pinfunction "20_20") (pintype "passive"))
      (node (ref "RS10") (pin "1") (pinfunction "1_1") (pintype "passive"))
    )
    (net (code "23") (name "B10OUT") (class "Default")
      (node (ref "Q10") (pin "D") (pinfunction "D_D") (pintype "passive"))
      (node (ref "X3") (pin "5") (pinfunction "KL_5") (pintype "passive"))
    )
    (net (code "24") (name "B11") (class "Default")
      (node (ref "JP1") (pin "21") (pinfunction "21_21") (pintype "passive"))
      (node (ref "JP1") (pin "22") (pinfunction "22_22") (pintype "passive"))
      (node (ref "RS11") (pin "1") (pinfunction "1_1") (pintype "passive"))
    )
    (net (code "25") (name "B11OUT") (class "Default")
      (node (ref "Q11") (pin "D") (pinfunction "D_D") (pintype "passive"))
      (node (ref "X3") (pin "4") (pinfunction "KL_4") (pintype "passive"))
    )
    (net (code "26") (name "B12") (class "Default")
      (node (ref "JP1") (pin "23") (pinfunction "23_23") (pintype "passive"))
      (node (ref "JP1") (pin "24") (pinfunction "24_24") (pintype "passive"))
      (node (ref "RS12") (pin "1") (pinfunction "1_1") (pintype "passive"))
    )
    (net (code "27") (name "B12OUT") (class "Default")
      (node (ref "Q12") (pin "D") (pinfunction "D_D") (pintype "passive"))
      (node (ref "X3") (pin "3") (pinfunction "KL_3") (pintype "passive"))
    )
    (net (code "28") (name "B13") (class "Default")
      (node (ref "JP1") (pin "25") (pinfunction "25_25") (pintype "passive"))
      (node (ref "JP1") (pin "26") (pinfunction "26_26") (pintype "passive"))
      (node (ref "RS14") (pin "1") (pinfunction "1_1") (pintype "passive"))
    )
    (net (code "29") (name "B13OUT") (class "Default")
      (node (ref "Q13") (pin "D") (pinfunction "D_D") (pintype "passive"))
      (node (ref "X3") (pin "2") (pinfunction "KL_2") (pintype "passive"))
    )
    (net (code "30") (name "B14") (class "Default")
      (node (ref "JP1") (pin "27") (pinfunction "27_27") (pintype "passive"))
      (node (ref "JP1") (pin "28") (pinfunction "28_28") (pintype "passive"))
      (node (ref "RS13") (pin "1") (pinfunction "1_1") (pintype "passive"))
    )
    (net (code "31") (name "B14OUT") (class "Default")
      (node (ref "Q14") (pin "D") (pinfunction "D_D") (pintype "passive"))
      (node (ref "X3") (pin "1") (pinfunction "KL_1") (pintype "passive"))
    )
    (net (code "32") (name "HAL-") (class "Default")
      (node (ref "Q1") (pin "D") (pinfunction "D_D") (pintype "passive"))
      (node (ref "U1") (pin "3") (pinfunction "IP-_3") (pintype "passive"))
      (node (ref "U1") (pin "4") (pinfunction "IP-_4") (pintype "passive"))
      (node (ref "X1") (pin "1") (pinfunction "KL_1") (pintype "passive"))
      (node (ref "X1") (pin "2") (pinfunction "KL_2") (pintype "passive"))
      (node (ref "X1") (pin "3") (pinfunction "KL_3") (pintype "passive"))
      (node (ref "X1") (pin "4") (pinfunction "KL_4") (pintype "passive"))
      (node (ref "X1") (pin "5") (pinfunction "KL_5") (pintype "passive"))
      (node (ref "X1") (pin "6") (pinfunction "KL_6") (pintype "passive"))
      (node (ref "X1") (pin "7") (pinfunction "KL_7") (pintype "passive"))
      (node (ref "X1") (pin "8") (pinfunction "KL_8") (pintype "passive"))
      (node (ref "X2") (pin "1") (pinfunction "KL_1") (pintype "passive"))
      (node (ref "X2") (pin "2") (pinfunction "KL_2") (pintype "passive"))
      (node (ref "X2") (pin "3") (pinfunction "KL_3") (pintype "passive"))
      (node (ref "X2") (pin "4") (pinfunction "KL_4") (pintype "passive"))
      (node (ref "X2") (pin "5") (pinfunction "KL_5") (pintype "passive"))
      (node (ref "X2") (pin "6") (pinfunction "KL_6") (pintype "passive"))
      (node (ref "X2") (pin "7") (pinfunction "KL_7") (pintype "passive"))
      (node (ref "X2") (pin "8") (pinfunction "KL_8") (pintype "passive"))
    )
    (net (code "33") (name "I_PV") (class "Default")
      (node (ref "JP2") (pin "5") (pinfunction "5_5") (pintype "passive"))
      (node (ref "JP2") (pin "6") (pinfunction "6_6") (pintype "passive"))
      (node (ref "U1") (pin "7") (pinfunction "VIOUT_7") (pintype "output"))
    )
    (net (code "34") (name "N$22") (class "Default")
      (node (ref "X3") (pin "8") (pinfunction "KL_8") (pintype "passive"))
    )
    (net (code "35") (name "N$23") (class "Default")
      (node (ref "X4") (pin "1") (pinfunction "KL_1") (pintype "passive"))
    )
    (net (code "36") (name "Net-(GD1-IN)") (class "Default")
      (node (ref "GD1") (pin "3") (pinfunction "IN_3") (pintype "input"))
      (node (ref "RS1") (pin "2") (pinfunction "2_2") (pintype "passive"))
    )
    (net (code "37") (name "Net-(GD1-OUT{slash}~{OUT})") (class "Default")
      (node (ref "GD1") (pin "5") (pinfunction "OUT/~{OUT}_5") (pintype "output"))
      (node (ref "RG1") (pin "2") (pinfunction "2_2") (pintype "passive"))
    )
    (net (code "38") (name "Net-(GD2-IN)") (class "Default")
      (node (ref "GD2") (pin "3") (pinfunction "IN_3") (pintype "input"))
      (node (ref "RS2") (pin "2") (pinfunction "2_2") (pintype "passive"))
    )
    (net (code "39") (name "Net-(GD2-OUT{slash}~{OUT})") (class "Default")
      (node (ref "GD2") (pin "5") (pinfunction "OUT/~{OUT}_5") (pintype "output"))
      (node (ref "RG2") (pin "2") (pinfunction "2_2") (pintype "passive"))
    )
    (net (code "40") (name "Net-(GD3-IN)") (class "Default")
      (node (ref "GD3") (pin "3") (pinfunction "IN_3") (pintype "input"))
      (node (ref "RS3") (pin "2") (pinfunction "2_2") (pintype "passive"))
    )
    (net (code "41") (name "Net-(GD3-OUT{slash}~{OUT})") (class "Default")
      (node (ref "GD3") (pin "5") (pinfunction "OUT/~{OUT}_5") (pintype "output"))
      (node (ref "RG3") (pin "2") (pinfunction "2_2") (pintype "passive"))
    )
    (net (code "42") (name "Net-(GD4-IN)") (class "Default")
      (node (ref "GD4") (pin "3") (pinfunction "IN_3") (pintype "input"))
      (node (ref "RS4") (pin "2") (pinfunction "2_2") (pintype "passive"))
    )
    (net (code "43") (name "Net-(GD4-OUT{slash}~{OUT})") (class "Default")
      (node (ref "GD4") (pin "5") (pinfunction "OUT/~{OUT}_5") (pintype "output"))
      (node (ref "RG4") (pin "2") (pinfunction "2_2") (pintype "passive"))
    )
    (net (code "44") (name "Net-(GD5-IN)") (class "Default")
      (node (ref "GD5") (pin "3") (pinfunction "IN_3") (pintype "input"))
      (node (ref "RS5") (pin "2") (pinfunction "2_2") (pintype "passive"))
    )
    (net (code "45") (name "Net-(GD5-OUT{slash}~{OUT})") (class "Default")
      (node (ref "GD5") (pin "5") (pinfunction "OUT/~{OUT}_5") (pintype "output"))
      (node (ref "RG5") (pin "2") (pinfunction "2_2") (pintype "passive"))
    )
    (net (code "46") (name "Net-(GD6-IN)") (class "Default")
      (node (ref "GD6") (pin "3") (pinfunction "IN_3") (pintype "input"))
      (node (ref "RS6") (pin "2") (pinfunction "2_2") (pintype "passive"))
    )
    (net (code "47") (name "Net-(GD6-OUT{slash}~{OUT})") (class "Default")
      (node (ref "GD6") (pin "5") (pinfunction "OUT/~{OUT}_5") (pintype "output"))
      (node (ref "RG6") (pin "2") (pinfunction "2_2") (pintype "passive"))
    )
    (net (code "48") (name "Net-(GD7-IN)") (class "Default")
      (node (ref "GD7") (pin "3") (pinfunction "IN_3") (pintype "input"))
      (node (ref "RS7") (pin "2") (pinfunction "2_2") (pintype "passive"))
    )
    (net (code "49") (name "Net-(GD7-OUT{slash}~{OUT})") (class "Default")
      (node (ref "GD7") (pin "5") (pinfunction "OUT/~{OUT}_5") (pintype "output"))
      (node (ref "RG7") (pin "2") (pinfunction "2_2") (pintype "passive"))
    )
    (net (code "50") (name "Net-(GD8-IN)") (class "Default")
      (node (ref "GD8") (pin "3") (pinfunction "IN_3") (pintype "input"))
      (node (ref "RS8") (pin "2") (pinfunction "2_2") (pintype "passive"))
    )
    (net (code "51") (name "Net-(GD8-OUT{slash}~{OUT})") (class "Default")
      (node (ref "GD8") (pin "5") (pinfunction "OUT/~{OUT}_5") (pintype "output"))
      (node (ref "RG8") (pin "2") (pinfunction "2_2") (pintype "passive"))
    )
    (net (code "52") (name "Net-(GD9-IN)") (class "Default")
      (node (ref "GD9") (pin "3") (pinfunction "IN_3") (pintype "input"))
      (node (ref "RS9") (pin "2") (pinfunction "2_2") (pintype "passive"))
    )
    (net (code "53") (name "Net-(GD9-OUT{slash}~{OUT})") (class "Default")
      (node (ref "GD9") (pin "5") (pinfunction "OUT/~{OUT}_5") (pintype "output"))
      (node (ref "RG9") (pin "2") (pinfunction "2_2") (pintype "passive"))
    )
    (net (code "54") (name "Net-(GD10-IN)") (class "Default")
      (node (ref "GD10") (pin "3") (pinfunction "IN_3") (pintype "input"))
      (node (ref "RS10") (pin "2") (pinfunction "2_2") (pintype "passive"))
    )
    (net (code "55") (name "Net-(GD10-OUT{slash}~{OUT})") (class "Default")
      (node (ref "GD10") (pin "5") (pinfunction "OUT/~{OUT}_5") (pintype "output"))
      (node (ref "RG10") (pin "2") (pinfunction "2_2") (pintype "passive"))
    )
    (net (code "56") (name "Net-(GD11-IN)") (class "Default")
      (node (ref "GD11") (pin "3") (pinfunction "IN_3") (pintype "input"))
      (node (ref "RS11") (pin "2") (pinfunction "2_2") (pintype "passive"))
    )
    (net (code "57") (name "Net-(GD11-OUT{slash}~{OUT})") (class "Default")
      (node (ref "GD11") (pin "5") (pinfunction "OUT/~{OUT}_5") (pintype "output"))
      (node (ref "RG11") (pin "2") (pinfunction "2_2") (pintype "passive"))
    )
    (net (code "58") (name "Net-(GD12-IN)") (class "Default")
      (node (ref "GD12") (pin "3") (pinfunction "IN_3") (pintype "input"))
      (node (ref "RS12") (pin "2") (pinfunction "2_2") (pintype "passive"))
    )
    (net (code "59") (name "Net-(GD12-OUT{slash}~{OUT})") (class "Default")
      (node (ref "GD12") (pin "5") (pinfunction "OUT/~{OUT}_5") (pintype "output"))
      (node (ref "RG12") (pin "2") (pinfunction "2_2") (pintype "passive"))
    )
    (net (code "60") (name "Net-(GD13-IN)") (class "Default")
      (node (ref "GD13") (pin "3") (pinfunction "IN_3") (pintype "input"))
      (node (ref "RS13") (pin "2") (pinfunction "2_2") (pintype "passive"))
    )
    (net (code "61") (name "Net-(GD13-OUT{slash}~{OUT})") (class "Default")
      (node (ref "GD13") (pin "5") (pinfunction "OUT/~{OUT}_5") (pintype "output"))
      (node (ref "RG13") (pin "2") (pinfunction "2_2") (pintype "passive"))
    )
    (net (code "62") (name "Net-(GD14-IN)") (class "Default")
      (node (ref "GD14") (pin "3") (pinfunction "IN_3") (pintype "input"))
      (node (ref "RS14") (pin "2") (pinfunction "2_2") (pintype "passive"))
    )
    (net (code "63") (name "Net-(GD14-OUT{slash}~{OUT})") (class "Default")
      (node (ref "GD14") (pin "5") (pinfunction "OUT/~{OUT}_5") (pintype "output"))
      (node (ref "RG14") (pin "2") (pinfunction "2_2") (pintype "passive"))
    )
    (net (code "64") (name "Net-(IC3A-+IN)") (class "Default")
      (node (ref "C19") (pin "1") (pinfunction "1_1") (pintype "passive"))
      (node (ref "D2") (pin "C") (pinfunction "C_C") (pintype "passive"))
      (node (ref "D3") (pin "A") (pinfunction "A_A") (pintype "passive"))
      (node (ref "IC3") (pin "3") (pinfunction "+IN_3") (pintype "input"))
      (node (ref "R2") (pin "2") (pinfunction "2_2") (pintype "passive"))
      (node (ref "R3") (pin "1") (pinfunction "1_1") (pintype "passive"))
    )
    (net (code "65") (name "Net-(Q1-PadG)") (class "Default")
      (node (ref "Q1") (pin "G") (pinfunction "G_G") (pintype "passive"))
      (node (ref "RG1") (pin "1") (pinfunction "1_1") (pintype "passive"))
    )
    (net (code "66") (name "Net-(Q2-PadG)") (class "Default")
      (node (ref "Q2") (pin "G") (pinfunction "G_G") (pintype "passive"))
      (node (ref "RG2") (pin "1") (pinfunction "1_1") (pintype "passive"))
    )
    (net (code "67") (name "Net-(Q3-PadG)") (class "Default")
      (node (ref "Q3") (pin "G") (pinfunction "G_G") (pintype "passive"))
      (node (ref "RG3") (pin "1") (pinfunction "1_1") (pintype "passive"))
    )
    (net (code "68") (name "Net-(Q4-PadG)") (class "Default")
      (node (ref "Q4") (pin "G") (pinfunction "G_G") (pintype "passive"))
      (node (ref "RG4") (pin "1") (pinfunction "1_1") (pintype "passive"))
    )
    (net (code "69") (name "Net-(Q5-PadG)") (class "Default")
      (node (ref "Q5") (pin "G") (pinfunction "G_G") (pintype "passive"))
      (node (ref "RG5") (pin "1") (pinfunction "1_1") (pintype "passive"))
    )
    (net (code "70") (name "Net-(Q6-PadG)") (class "Default")
      (node (ref "Q6") (pin "G") (pinfunction "G_G") (pintype "passive"))
      (node (ref "RG6") (pin "1") (pinfunction "1_1") (pintype "passive"))
    )
    (net (code "71") (name "Net-(Q7-PadG)") (class "Default")
      (node (ref "Q7") (pin "G") (pinfunction "G_G") (pintype "passive"))
      (node (ref "RG7") (pin "1") (pinfunction "1_1") (pintype "passive"))
    )
    (net (code "72") (name "Net-(Q8-PadG)") (class "Default")
      (node (ref "Q8") (pin "G") (pinfunction "G_G") (pintype "passive"))
      (node (ref "RG8") (pin "1") (pinfunction "1_1") (pintype "passive"))
    )
    (net (code "73") (name "Net-(Q9-PadG)") (class "Default")
      (node (ref "Q9") (pin "G") (pinfunction "G_G") (pintype "passive"))
      (node (ref "RG9") (pin "1") (pinfunction "1_1") (pintype "passive"))
    )
    (net (code "74") (name "Net-(Q10-PadG)") (class "Default")
      (node (ref "Q10") (pin "G") (pinfunction "G_G") (pintype "passive"))
      (node (ref "RG10") (pin "1") (pinfunction "1_1") (pintype "passive"))
    )
    (net (code "75") (name "Net-(Q11-PadG)") (class "Default")
      (node (ref "Q11") (pin "G") (pinfunction "G_G") (pintype "passive"))
      (node (ref "RG11") (pin "1") (pinfunction "1_1") (pintype "passive"))
    )
    (net (code "76") (name "Net-(Q12-PadG)") (class "Default")
      (node (ref "Q12") (pin "G") (pinfunction "G_G") (pintype "passive"))
      (node (ref "RG12") (pin "1") (pinfunction "1_1") (pintype "passive"))
    )
    (net (code "77") (name "Net-(Q13-PadG)") (class "Default")
      (node (ref "Q13") (pin "G") (pinfunction "G_G") (pintype "passive"))
      (node (ref "RG13") (pin "1") (pinfunction "1_1") (pintype "passive"))
    )
    (net (code "78") (name "Net-(Q14-PadG)") (class "Default")
      (node (ref "Q14") (pin "G") (pinfunction "G_G") (pintype "passive"))
      (node (ref "RG14") (pin "1") (pinfunction "1_1") (pintype "passive"))
    )
    (net (code "79") (name "Net-(U1-FILTER)") (class "Default")
      (node (ref "C20") (pin "1") (pinfunction "1_1") (pintype "passive"))
      (node (ref "U1") (pin "6") (pinfunction "FILTER_6") (pintype "passive"))
    )
    (net (code "80") (name "PGND") (class "Default")
      (node (ref "PV") (pin "2") (pinfunction "KL_2") (pintype "passive"))
      (node (ref "Q1") (pin "S") (pinfunction "S_S") (pintype "passive"))
      (node (ref "Q10") (pin "S") (pinfunction "S_S") (pintype "passive"))
      (node (ref "Q11") (pin "S") (pinfunction "S_S") (pintype "passive"))
      (node (ref "Q12") (pin "S") (pinfunction "S_S") (pintype "passive"))
      (node (ref "Q13") (pin "S") (pinfunction "S_S") (pintype "passive"))
      (node (ref "Q14") (pin "S") (pinfunction "S_S") (pintype "passive"))
      (node (ref "Q2") (pin "S") (pinfunction "S_S") (pintype "passive"))
      (node (ref "Q3") (pin "S") (pinfunction "S_S") (pintype "passive"))
      (node (ref "Q4") (pin "S") (pinfunction "S_S") (pintype "passive"))
      (node (ref "Q5") (pin "S") (pinfunction "S_S") (pintype "passive"))
      (node (ref "Q6") (pin "S") (pinfunction "S_S") (pintype "passive"))
      (node (ref "Q7") (pin "S") (pinfunction "S_S") (pintype "passive"))
      (node (ref "Q8") (pin "S") (pinfunction "S_S") (pintype "passive"))
      (node (ref "Q9") (pin "S") (pinfunction "S_S") (pintype "passive"))
    )
    (net (code "81") (name "PV+") (class "Default")
      (node (ref "PV") (pin "1") (pinfunction "KL_1") (pintype "passive"))
      (node (ref "R2") (pin "1") (pinfunction "1_1") (pintype "passive"))
      (node (ref "U1") (pin "1") (pinfunction "IP+_1") (pintype "passive"))
      (node (ref "U1") (pin "2") (pinfunction "IP+_2") (pintype "passive"))
    )
    (net (code "82") (name "V_PV") (class "Default")
      (node (ref "C23") (pin "1") (pinfunction "1_1") (pintype "passive"))
      (node (ref "IC3") (pin "1") (pinfunction "OUT_1") (pintype "output"))
      (node (ref "IC3") (pin "2") (pinfunction "-IN_2") (pintype "input"))
      (node (ref "JP2") (pin "3") (pinfunction "3_3") (pintype "passive"))
      (node (ref "JP2") (pin "4") (pinfunction "4_4") (pintype "passive"))
    )
  )
)
